# control_board-mixed-v2.net
KiCad netlist of a schematic drawn in EAGLE
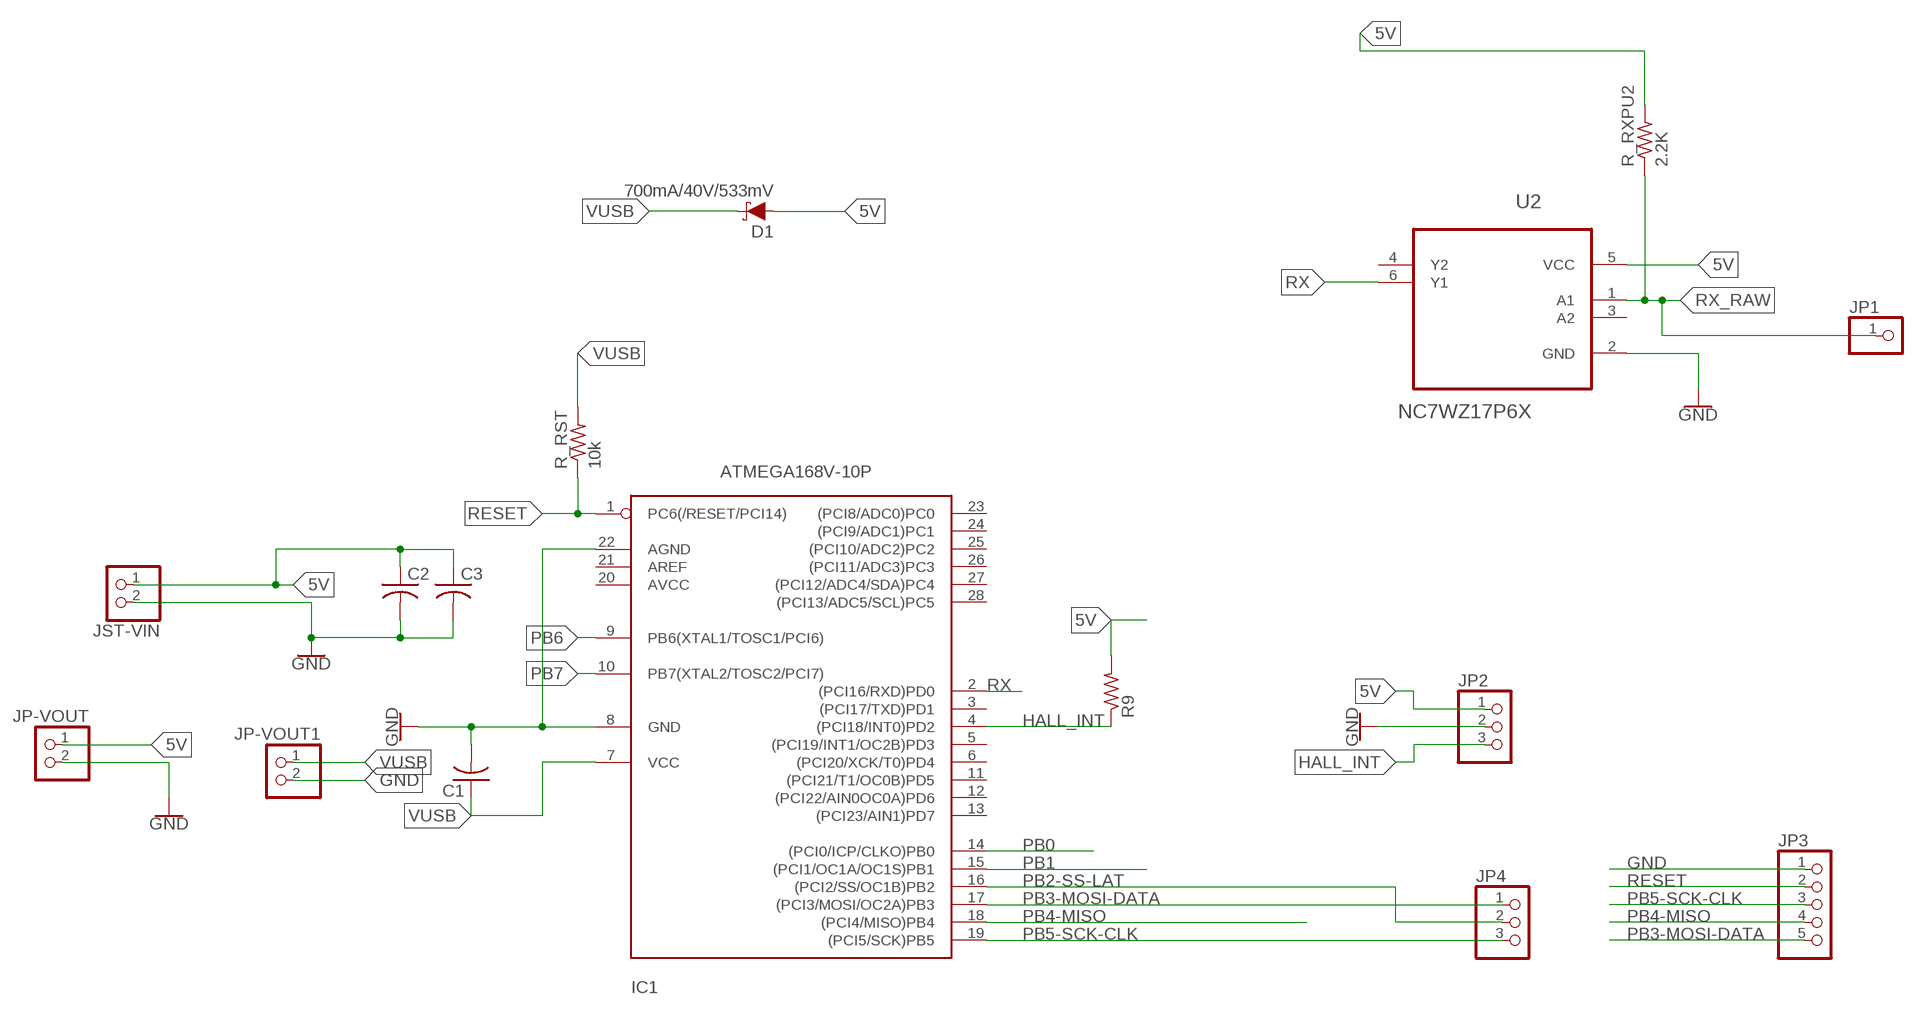
[diagram p0: schematic, sheet 1]

(export (version "E")
  (design (tool "Eeschema 10.0.6"))
  (components
    (comp (ref "C1")
      (value "C-US025-030X050")
      (footprint "eagle-import:C025-030X050")
      (libsource (lib "eagle-import") (part "C-US025-030X050"))
    )
    (comp (ref "C2")
      (value "C-US025-060X050")
      (footprint "eagle-import:C025-060X050")
      (libsource (lib "eagle-import") (part "C-US025-060X050"))
    )
    (comp (ref "C3")
      (value "C-US025-060X050")
      (footprint "eagle-import:C025-060X050")
      (libsource (lib "eagle-import") (part "C-US025-060X050"))
    )
    (comp (ref "D1")
      (value "700mA/40V/533mV")
      (footprint "eagle-import:SOT23-3")
      (libsource (lib "eagle-import") (part "DIODE-SCHOTTKY-ZLLS500"))
    )
    (comp (ref "IC1")
      (value "ATMEGA168V-10P")
      (footprint "eagle-import:DIL28-3")
      (libsource (lib "eagle-import") (part "ATMEGA168PV-10"))
    )
    (comp (ref "JP-VOUT")
      (value "PINHD-1X2")
      (footprint "eagle-import:1X02")
      (libsource (lib "eagle-import") (part "PINHD-1X2"))
    )
    (comp (ref "JP-VOUT1")
      (value "PINHD-1X2")
      (footprint "eagle-import:1X02")
      (libsource (lib "eagle-import") (part "PINHD-1X2"))
    )
    (comp (ref "JP1")
      (value "PINHD-1X1")
      (footprint "eagle-import:1X01")
      (libsource (lib "eagle-import") (part "PINHD-1X1"))
    )
    (comp (ref "JP2")
      (value "PINHD-1X3")
      (footprint "eagle-import:1X03")
      (libsource (lib "eagle-import") (part "PINHD-1X3"))
    )
    (comp (ref "JP3")
      (value "PINHD-1X5")
      (footprint "eagle-import:1X05")
      (libsource (lib "eagle-import") (part "PINHD-1X5"))
    )
    (comp (ref "JP4")
      (value "PINHD-1X3")
      (footprint "eagle-import:1X03")
      (libsource (lib "eagle-import") (part "PINHD-1X3"))
    )
    (comp (ref "JST-VIN")
      (value "JST_2PIN-THM-RA")
      (footprint "eagle-import:JST-PH-2-THM-RA")
      (libsource (lib "eagle-import") (part "JST_2PIN-THM-RA"))
    )
    (comp (ref "R9")
      (value "R-US_0207/7")
      (footprint "eagle-import:0207_7")
      (libsource (lib "eagle-import") (part "R-US_0207/7"))
    )
    (comp (ref "R_RST")
      (value "10k")
      (footprint "eagle-import:R0603")
      (libsource (lib "eagle-import") (part "R-US_R0603"))
    )
    (comp (ref "R_RXPU2")
      (value "2.2K")
      (footprint "eagle-import:R0603")
      (libsource (lib "eagle-import") (part "R-US_R0603"))
    )
    (comp (ref "U2")
      (value "NC7WZ17P6X")
      (footprint "eagle-import:SOT65P210X110-6N")
      (fields (field (name "MF") "Fairchild Semiconductor"))
      (libsource (lib "eagle-import") (part "NC7WZ17P6X"))
    )
  )
  (nets
    (net (code "1") (name "/PB0") (class "Default")
      (node (ref "IC1") (pin "14") (pinfunction "(PCI0/ICP/CLKO)PB0_14") (pintype "bidirectional"))
    )
    (net (code "2") (name "/PB1") (class "Default")
      (node (ref "IC1") (pin "15") (pinfunction "(PCI1/OC1A/OC1S)PB1_15") (pintype "bidirectional"))
    )
    (net (code "3") (name "/PB2-SS-LAT") (class "Default")
      (node (ref "IC1") (pin "16") (pinfunction "(PCI2/SS/OC1B)PB2_16") (pintype "bidirectional"))
      (node (ref "JP4") (pin "2") (pinfunction "2_2") (pintype "passive"))
    )
    (net (code "4") (name "/PB3-MOSI-DATA") (class "Default")
      (node (ref "IC1") (pin "17") (pinfunction "(PCI3/MOSI/OC2A)PB3_17") (pintype "bidirectional"))
      (node (ref "JP3") (pin "5") (pinfunction "5_5") (pintype "passive"))
      (node (ref "JP4") (pin "1") (pinfunction "1_1") (pintype "passive"))
    )
    (net (code "5") (name "/PB4-MISO") (class "Default")
      (node (ref "IC1") (pin "18") (pinfunction "(PCI4/MISO)PB4_18") (pintype "bidirectional"))
      (node (ref "JP3") (pin "4") (pinfunction "4_4") (pintype "passive"))
    )
    (net (code "6") (name "/PB5-SCK-CLK") (class "Default")
      (node (ref "IC1") (pin "19") (pinfunction "(PCI5/SCK)PB5_19") (pintype "bidirectional"))
      (node (ref "JP3") (pin "3") (pinfunction "3_3") (pintype "passive"))
      (node (ref "JP4") (pin "3") (pinfunction "3_3") (pintype "passive"))
    )
    (net (code "7") (name "5V") (class "Default")
      (node (ref "C2") (pin "1") (pinfunction "1_1") (pintype "passive"))
      (node (ref "C3") (pin "1") (pinfunction "1_1") (pintype "passive"))
      (node (ref "D1") (pin "1") (pinfunction "A_1") (pintype "passive"))
      (node (ref "JP-VOUT") (pin "1") (pinfunction "1_1") (pintype "passive"))
      (node (ref "JP2") (pin "1") (pinfunction "1_1") (pintype "passive"))
      (node (ref "JST-VIN") (pin "1") (pinfunction "2_1") (pintype "passive"))
      (node (ref "R9") (pin "2") (pinfunction "2_2") (pintype "passive"))
      (node (ref "R_RXPU2") (pin "2") (pinfunction "2_2") (pintype "passive"))
      (node (ref "U2") (pin "5") (pinfunction "VCC_5") (pintype "power_in"))
    )
    (net (code "8") (name "GND") (class "Default")
      (node (ref "C1") (pin "2") (pinfunction "2_2") (pintype "passive"))
      (node (ref "C2") (pin "2") (pinfunction "2_2") (pintype "passive"))
      (node (ref "C3") (pin "2") (pinfunction "2_2") (pintype "passive"))
      (node (ref "IC1") (pin "22") (pinfunction "AGND_22") (pintype "bidirectional"))
      (node (ref "IC1") (pin "8") (pinfunction "GND_8") (pintype "bidirectional"))
      (node (ref "JP-VOUT") (pin "2") (pinfunction "2_2") (pintype "passive"))
      (node (ref "JP-VOUT1") (pin "2") (pinfunction "2_2") (pintype "passive"))
      (node (ref "JP2") (pin "2") (pinfunction "2_2") (pintype "passive"))
      (node (ref "JP3") (pin "1") (pinfunction "1_1") (pintype "passive"))
      (node (ref "JST-VIN") (pin "2") (pinfunction "1_2") (pintype "passive"))
      (node (ref "U2") (pin "2") (pinfunction "GND_2") (pintype "passive"))
    )
    (net (code "9") (name "HALL_INT") (class "Default")
      (node (ref "IC1") (pin "4") (pinfunction "(PCI18/INT0)PD2_4") (pintype "bidirectional"))
      (node (ref "JP2") (pin "3") (pinfunction "3_3") (pintype "passive"))
      (node (ref "R9") (pin "1") (pinfunction "1_1") (pintype "passive"))
    )
    (net (code "10") (name "PB6") (class "Default")
      (node (ref "IC1") (pin "9") (pinfunction "PB6(XTAL1/TOSC1/PCI6)_9") (pintype "bidirectional"))
    )
    (net (code "11") (name "PB7") (class "Default")
      (node (ref "IC1") (pin "10") (pinfunction "PB7(XTAL2/TOSC2/PCI7)_10") (pintype "bidirectional"))
    )
    (net (code "12") (name "RESET") (class "Default")
      (node (ref "IC1") (pin "1") (pinfunction "PC6(/RESET/PCI14)_1") (pintype "bidirectional"))
      (node (ref "JP3") (pin "2") (pinfunction "2_2") (pintype "passive"))
      (node (ref "R_RST") (pin "1") (pinfunction "1_1") (pintype "passive"))
    )
    (net (code "13") (name "RX") (class "Default")
      (node (ref "IC1") (pin "2") (pinfunction "(PCI16/RXD)PD0_2") (pintype "bidirectional"))
      (node (ref "U2") (pin "6") (pinfunction "Y1_6") (pintype "output"))
    )
    (net (code "14") (name "RX_RAW") (class "Default")
      (node (ref "JP1") (pin "1") (pinfunction "1_1") (pintype "passive"))
      (node (ref "R_RXPU2") (pin "1") (pinfunction "1_1") (pintype "passive"))
      (node (ref "U2") (pin "1") (pinfunction "A1_1") (pintype "input"))
    )
    (net (code "15") (name "VUSB") (class "Default")
      (node (ref "C1") (pin "1") (pinfunction "1_1") (pintype "passive"))
      (node (ref "D1") (pin "3") (pinfunction "C_3") (pintype "passive"))
      (node (ref "IC1") (pin "7") (pinfunction "VCC_7") (pintype "bidirectional"))
      (node (ref "JP-VOUT1") (pin "1") (pinfunction "1_1") (pintype "passive"))
      (node (ref "R_RST") (pin "2") (pinfunction "2_2") (pintype "passive"))
    )
    (net (code "16") (name "unconnected-(IC1-(PCI8{slash}ADC0)PC0-Pad23)") (class "Default")
      (node (ref "IC1") (pin "23") (pinfunction "(PCI8/ADC0)PC0_23") (pintype "bidirectional"))
    )
    (net (code "17") (name "unconnected-(IC1-(PCI9{slash}ADC1)PC1-Pad24)") (class "Default")
      (node (ref "IC1") (pin "24") (pinfunction "(PCI9/ADC1)PC1_24") (pintype "bidirectional"))
    )
    (net (code "18") (name "unconnected-(IC1-(PCI10{slash}ADC2)PC2-Pad25)") (class "Default")
      (node (ref "IC1") (pin "25") (pinfunction "(PCI10/ADC2)PC2_25") (pintype "bidirectional"))
    )
    (net (code "19") (name "unconnected-(IC1-(PCI11{slash}ADC3)PC3-Pad26)") (class "Default")
      (node (ref "IC1") (pin "26") (pinfunction "(PCI11/ADC3)PC3_26") (pintype "bidirectional"))
    )
    (net (code "20") (name "unconnected-(IC1-(PCI12{slash}ADC4{slash}SDA)PC4-Pad27)") (class "Default")
      (node (ref "IC1") (pin "27") (pinfunction "(PCI12/ADC4/SDA)PC4_27") (pintype "bidirectional"))
    )
    (net (code "21") (name "unconnected-(IC1-(PCI13{slash}ADC5{slash}SCL)PC5-Pad28)") (class "Default")
      (node (ref "IC1") (pin "28") (pinfunction "(PCI13/ADC5/SCL)PC5_28") (pintype "bidirectional"))
    )
    (net (code "22") (name "unconnected-(IC1-(PCI17{slash}TXD)PD1-Pad3)") (class "Default")
      (node (ref "IC1") (pin "3") (pinfunction "(PCI17/TXD)PD1_3") (pintype "bidirectional"))
    )
    (net (code "23") (name "unconnected-(IC1-(PCI19{slash}INT1{slash}OC2B)PD3-Pad5)") (class "Default")
      (node (ref "IC1") (pin "5") (pinfunction "(PCI19/INT1/OC2B)PD3_5") (pintype "bidirectional"))
    )
    (net (code "24") (name "unconnected-(IC1-(PCI20{slash}XCK{slash}T0)PD4-Pad6)") (class "Default")
      (node (ref "IC1") (pin "6") (pinfunction "(PCI20/XCK/T0)PD4_6") (pintype "bidirectional"))
    )
    (net (code "25") (name "unconnected-(IC1-(PCI21{slash}T1{slash}OC0B)PD5-Pad11)") (class "Default")
      (node (ref "IC1") (pin "11") (pinfunction "(PCI21/T1/OC0B)PD5_11") (pintype "bidirectional"))
    )
    (net (code "26") (name "unconnected-(IC1-(PCI22{slash}AIN0OC0A)PD6-Pad12)") (class "Default")
      (node (ref "IC1") (pin "12") (pinfunction "(PCI22/AIN0OC0A)PD6_12") (pintype "bidirectional"))
    )
    (net (code "27") (name "unconnected-(IC1-(PCI23{slash}AIN1)PD7-Pad13)") (class "Default")
      (node (ref "IC1") (pin "13") (pinfunction "(PCI23/AIN1)PD7_13") (pintype "bidirectional"))
    )
    (net (code "28") (name "unconnected-(IC1-AREF-Pad21)") (class "Default")
      (node (ref "IC1") (pin "21") (pinfunction "AREF_21") (pintype "bidirectional"))
    )
    (net (code "29") (name "unconnected-(IC1-AVCC-Pad20)") (class "Default")
      (node (ref "IC1") (pin "20") (pinfunction "AVCC_20") (pintype "bidirectional"))
    )
    (net (code "30") (name "unconnected-(U2-A2-Pad3)") (class "Default")
      (node (ref "U2") (pin "3") (pinfunction "A2_3") (pintype "input"))
    )
    (net (code "31") (name "unconnected-(U2-Y2-Pad4)") (class "Default")
      (node (ref "U2") (pin "4") (pinfunction "Y2_4") (pintype "output"))
    )
  )
)
